# H3_SWPad_Small_Rev_3.net
KiCad netlist of a schematic drawn in EAGLE
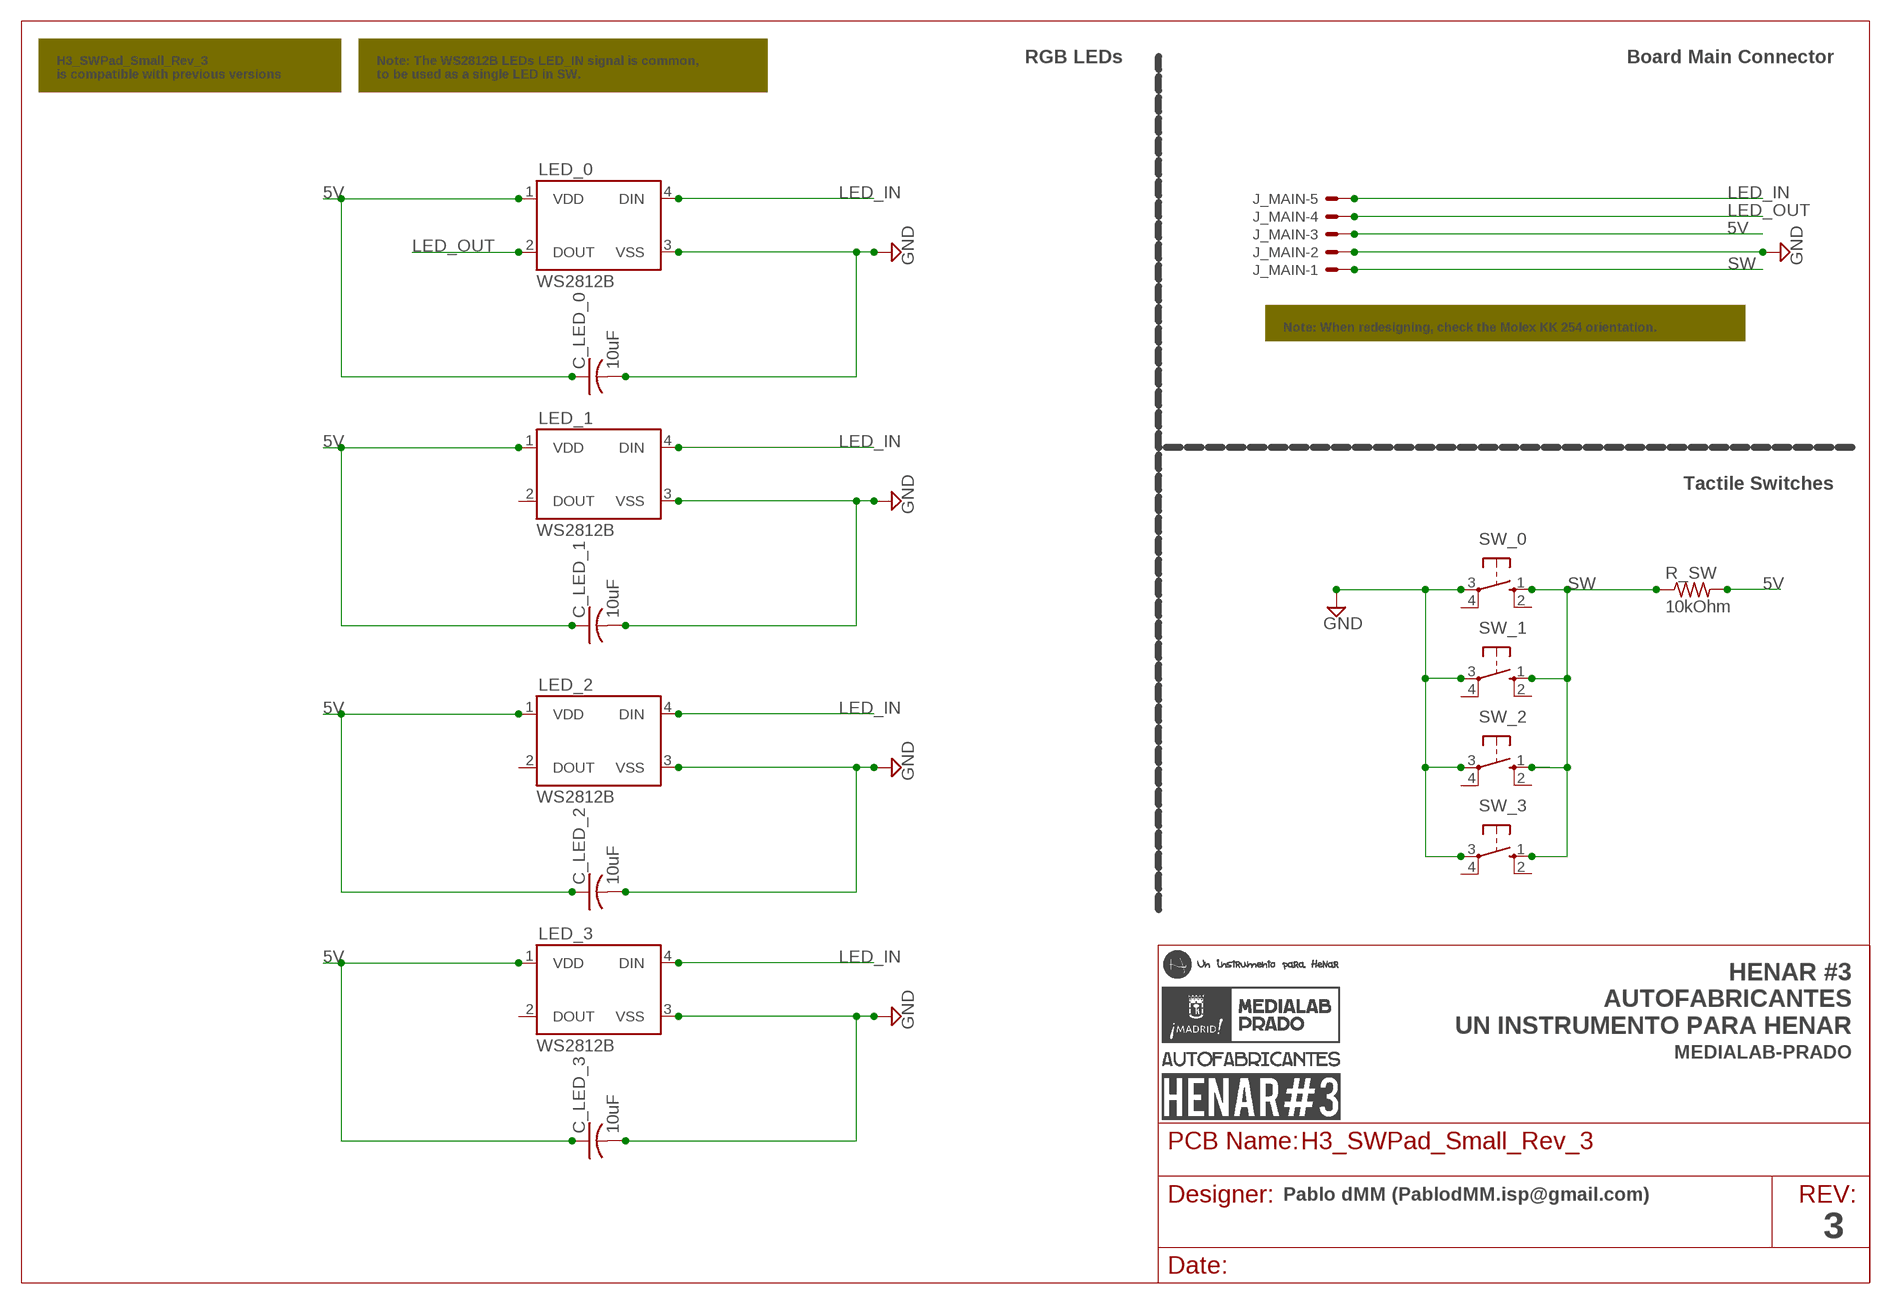
[diagram p0: schematic, sheet 1]

(export (version "E")
  (design (tool "Eeschema 10.0.6"))
  (components
    (comp (ref "C_LED_0")
      (value "10uF")
      (footprint "eagle-import:C1206K")
      (libsource (lib "eagle-import") (part "C-USC1206K"))
    )
    (comp (ref "C_LED_1")
      (value "10uF")
      (footprint "eagle-import:C1206K")
      (libsource (lib "eagle-import") (part "C-USC1206K"))
    )
    (comp (ref "C_LED_2")
      (value "10uF")
      (footprint "eagle-import:C1206K")
      (libsource (lib "eagle-import") (part "C-USC1206K"))
    )
    (comp (ref "C_LED_3")
      (value "10uF")
      (footprint "eagle-import:C1206K")
      (libsource (lib "eagle-import") (part "C-USC1206K"))
    )
    (comp (ref "J_MAIN")
      (value "22-05-7058-05")
      (footprint "eagle-import:7395-05")
      (libsource (lib "eagle-import") (part "22-?-0505-7058"))
    )
    (comp (ref "LED_0")
      (value "WS2812B")
      (footprint "eagle-import:WS2812B")
      (libsource (lib "eagle-import") (part "WS2812B"))
    )
    (comp (ref "LED_1")
      (value "WS2812B")
      (footprint "eagle-import:WS2812B")
      (libsource (lib "eagle-import") (part "WS2812B"))
    )
    (comp (ref "LED_2")
      (value "WS2812B")
      (footprint "eagle-import:WS2812B")
      (libsource (lib "eagle-import") (part "WS2812B"))
    )
    (comp (ref "LED_3")
      (value "WS2812B")
      (footprint "eagle-import:WS2812B")
      (libsource (lib "eagle-import") (part "WS2812B"))
    )
    (comp (ref "R_SW")
      (value "10kOhm")
      (footprint "eagle-import:R1206W")
      (libsource (lib "eagle-import") (part "R-US_R1206W"))
    )
    (comp (ref "SW_0")
      (value "10-XX")
      (footprint "eagle-import:B3F-10XX")
      (fields (field (name "MPN") "B3F-1000"))
      (libsource (lib "eagle-import") (part "10-XX"))
    )
    (comp (ref "SW_1")
      (value "10-XX")
      (footprint "eagle-import:B3F-10XX")
      (fields (field (name "MPN") "B3F-1000"))
      (libsource (lib "eagle-import") (part "10-XX"))
    )
    (comp (ref "SW_2")
      (value "10-XX")
      (footprint "eagle-import:B3F-10XX")
      (fields (field (name "MPN") "B3F-1000"))
      (libsource (lib "eagle-import") (part "10-XX"))
    )
    (comp (ref "SW_3")
      (value "10-XX")
      (footprint "eagle-import:B3F-10XX")
      (fields (field (name "MPN") "B3F-1000"))
      (libsource (lib "eagle-import") (part "10-XX"))
    )
  )
  (nets
    (net (code "1") (name "/5V") (class "Default")
      (node (ref "C_LED_0") (pin "1") (pinfunction "1_1") (pintype "passive"))
      (node (ref "C_LED_1") (pin "1") (pinfunction "1_1") (pintype "passive"))
      (node (ref "C_LED_2") (pin "1") (pinfunction "1_1") (pintype "passive"))
      (node (ref "C_LED_3") (pin "1") (pinfunction "1_1") (pintype "passive"))
      (node (ref "J_MAIN") (pin "3") (pinfunction "S_3") (pintype "passive"))
      (node (ref "LED_0") (pin "1") (pinfunction "VDD_1") (pintype "power_in"))
      (node (ref "LED_1") (pin "1") (pinfunction "VDD_1") (pintype "power_in"))
      (node (ref "LED_2") (pin "1") (pinfunction "VDD_1") (pintype "power_in"))
      (node (ref "LED_3") (pin "1") (pinfunction "VDD_1") (pintype "power_in"))
      (node (ref "R_SW") (pin "2") (pinfunction "2_2") (pintype "passive"))
    )
    (net (code "2") (name "/LED_IN") (class "Default")
      (node (ref "J_MAIN") (pin "5") (pinfunction "S_5") (pintype "passive"))
      (node (ref "LED_0") (pin "4") (pinfunction "DIN_4") (pintype "input"))
      (node (ref "LED_1") (pin "4") (pinfunction "DIN_4") (pintype "input"))
      (node (ref "LED_2") (pin "4") (pinfunction "DIN_4") (pintype "input"))
      (node (ref "LED_3") (pin "4") (pinfunction "DIN_4") (pintype "input"))
    )
    (net (code "3") (name "/LED_OUT") (class "Default")
      (node (ref "J_MAIN") (pin "4") (pinfunction "S_4") (pintype "passive"))
      (node (ref "LED_0") (pin "2") (pinfunction "DOUT_2") (pintype "output"))
    )
    (net (code "4") (name "/SW") (class "Default")
      (node (ref "J_MAIN") (pin "1") (pinfunction "S_1") (pintype "passive"))
      (node (ref "R_SW") (pin "1") (pinfunction "1_1") (pintype "passive"))
      (node (ref "SW_0") (pin "1") (pinfunction "S_1") (pintype "passive"))
      (node (ref "SW_1") (pin "1") (pinfunction "S_1") (pintype "passive"))
      (node (ref "SW_2") (pin "1") (pinfunction "S_1") (pintype "passive"))
      (node (ref "SW_3") (pin "1") (pinfunction "S_1") (pintype "passive"))
    )
    (net (code "5") (name "GND") (class "Default")
      (node (ref "C_LED_0") (pin "2") (pinfunction "2_2") (pintype "passive"))
      (node (ref "C_LED_1") (pin "2") (pinfunction "2_2") (pintype "passive"))
      (node (ref "C_LED_2") (pin "2") (pinfunction "2_2") (pintype "passive"))
      (node (ref "C_LED_3") (pin "2") (pinfunction "2_2") (pintype "passive"))
      (node (ref "J_MAIN") (pin "2") (pinfunction "S_2") (pintype "passive"))
      (node (ref "LED_0") (pin "3") (pinfunction "VSS_3") (pintype "power_in"))
      (node (ref "LED_1") (pin "3") (pinfunction "VSS_3") (pintype "power_in"))
      (node (ref "LED_2") (pin "3") (pinfunction "VSS_3") (pintype "power_in"))
      (node (ref "LED_3") (pin "3") (pinfunction "VSS_3") (pintype "power_in"))
      (node (ref "SW_0") (pin "3") (pinfunction "P_3") (pintype "passive"))
      (node (ref "SW_1") (pin "3") (pinfunction "P_3") (pintype "passive"))
      (node (ref "SW_2") (pin "3") (pinfunction "P_3") (pintype "passive"))
      (node (ref "SW_3") (pin "3") (pinfunction "P_3") (pintype "passive"))
    )
    (net (code "6") (name "unconnected-(LED_1-DOUT-Pad2)") (class "Default")
      (node (ref "LED_1") (pin "2") (pinfunction "DOUT_2") (pintype "output"))
    )
    (net (code "7") (name "unconnected-(LED_2-DOUT-Pad2)") (class "Default")
      (node (ref "LED_2") (pin "2") (pinfunction "DOUT_2") (pintype "output"))
    )
    (net (code "8") (name "unconnected-(LED_3-DOUT-Pad2)") (class "Default")
      (node (ref "LED_3") (pin "2") (pinfunction "DOUT_2") (pintype "output"))
    )
    (net (code "9") (name "unconnected-(SW_0-P1-Pad4)") (class "Default")
      (node (ref "SW_0") (pin "4") (pinfunction "P1_4") (pintype "passive"))
    )
    (net (code "10") (name "unconnected-(SW_0-S1-Pad2)") (class "Default")
      (node (ref "SW_0") (pin "2") (pinfunction "S1_2") (pintype "passive"))
    )
    (net (code "11") (name "unconnected-(SW_1-P1-Pad4)") (class "Default")
      (node (ref "SW_1") (pin "4") (pinfunction "P1_4") (pintype "passive"))
    )
    (net (code "12") (name "unconnected-(SW_1-S1-Pad2)") (class "Default")
      (node (ref "SW_1") (pin "2") (pinfunction "S1_2") (pintype "passive"))
    )
    (net (code "13") (name "unconnected-(SW_2-P1-Pad4)") (class "Default")
      (node (ref "SW_2") (pin "4") (pinfunction "P1_4") (pintype "passive"))
    )
    (net (code "14") (name "unconnected-(SW_2-S1-Pad2)") (class "Default")
      (node (ref "SW_2") (pin "2") (pinfunction "S1_2") (pintype "passive"))
    )
    (net (code "15") (name "unconnected-(SW_3-P1-Pad4)") (class "Default")
      (node (ref "SW_3") (pin "4") (pinfunction "P1_4") (pintype "passive"))
    )
    (net (code "16") (name "unconnected-(SW_3-S1-Pad2)") (class "Default")
      (node (ref "SW_3") (pin "2") (pinfunction "S1_2") (pintype "passive"))
    )
  )
)
